# main.net
KiCad netlist of a schematic drawn in Altium Designer
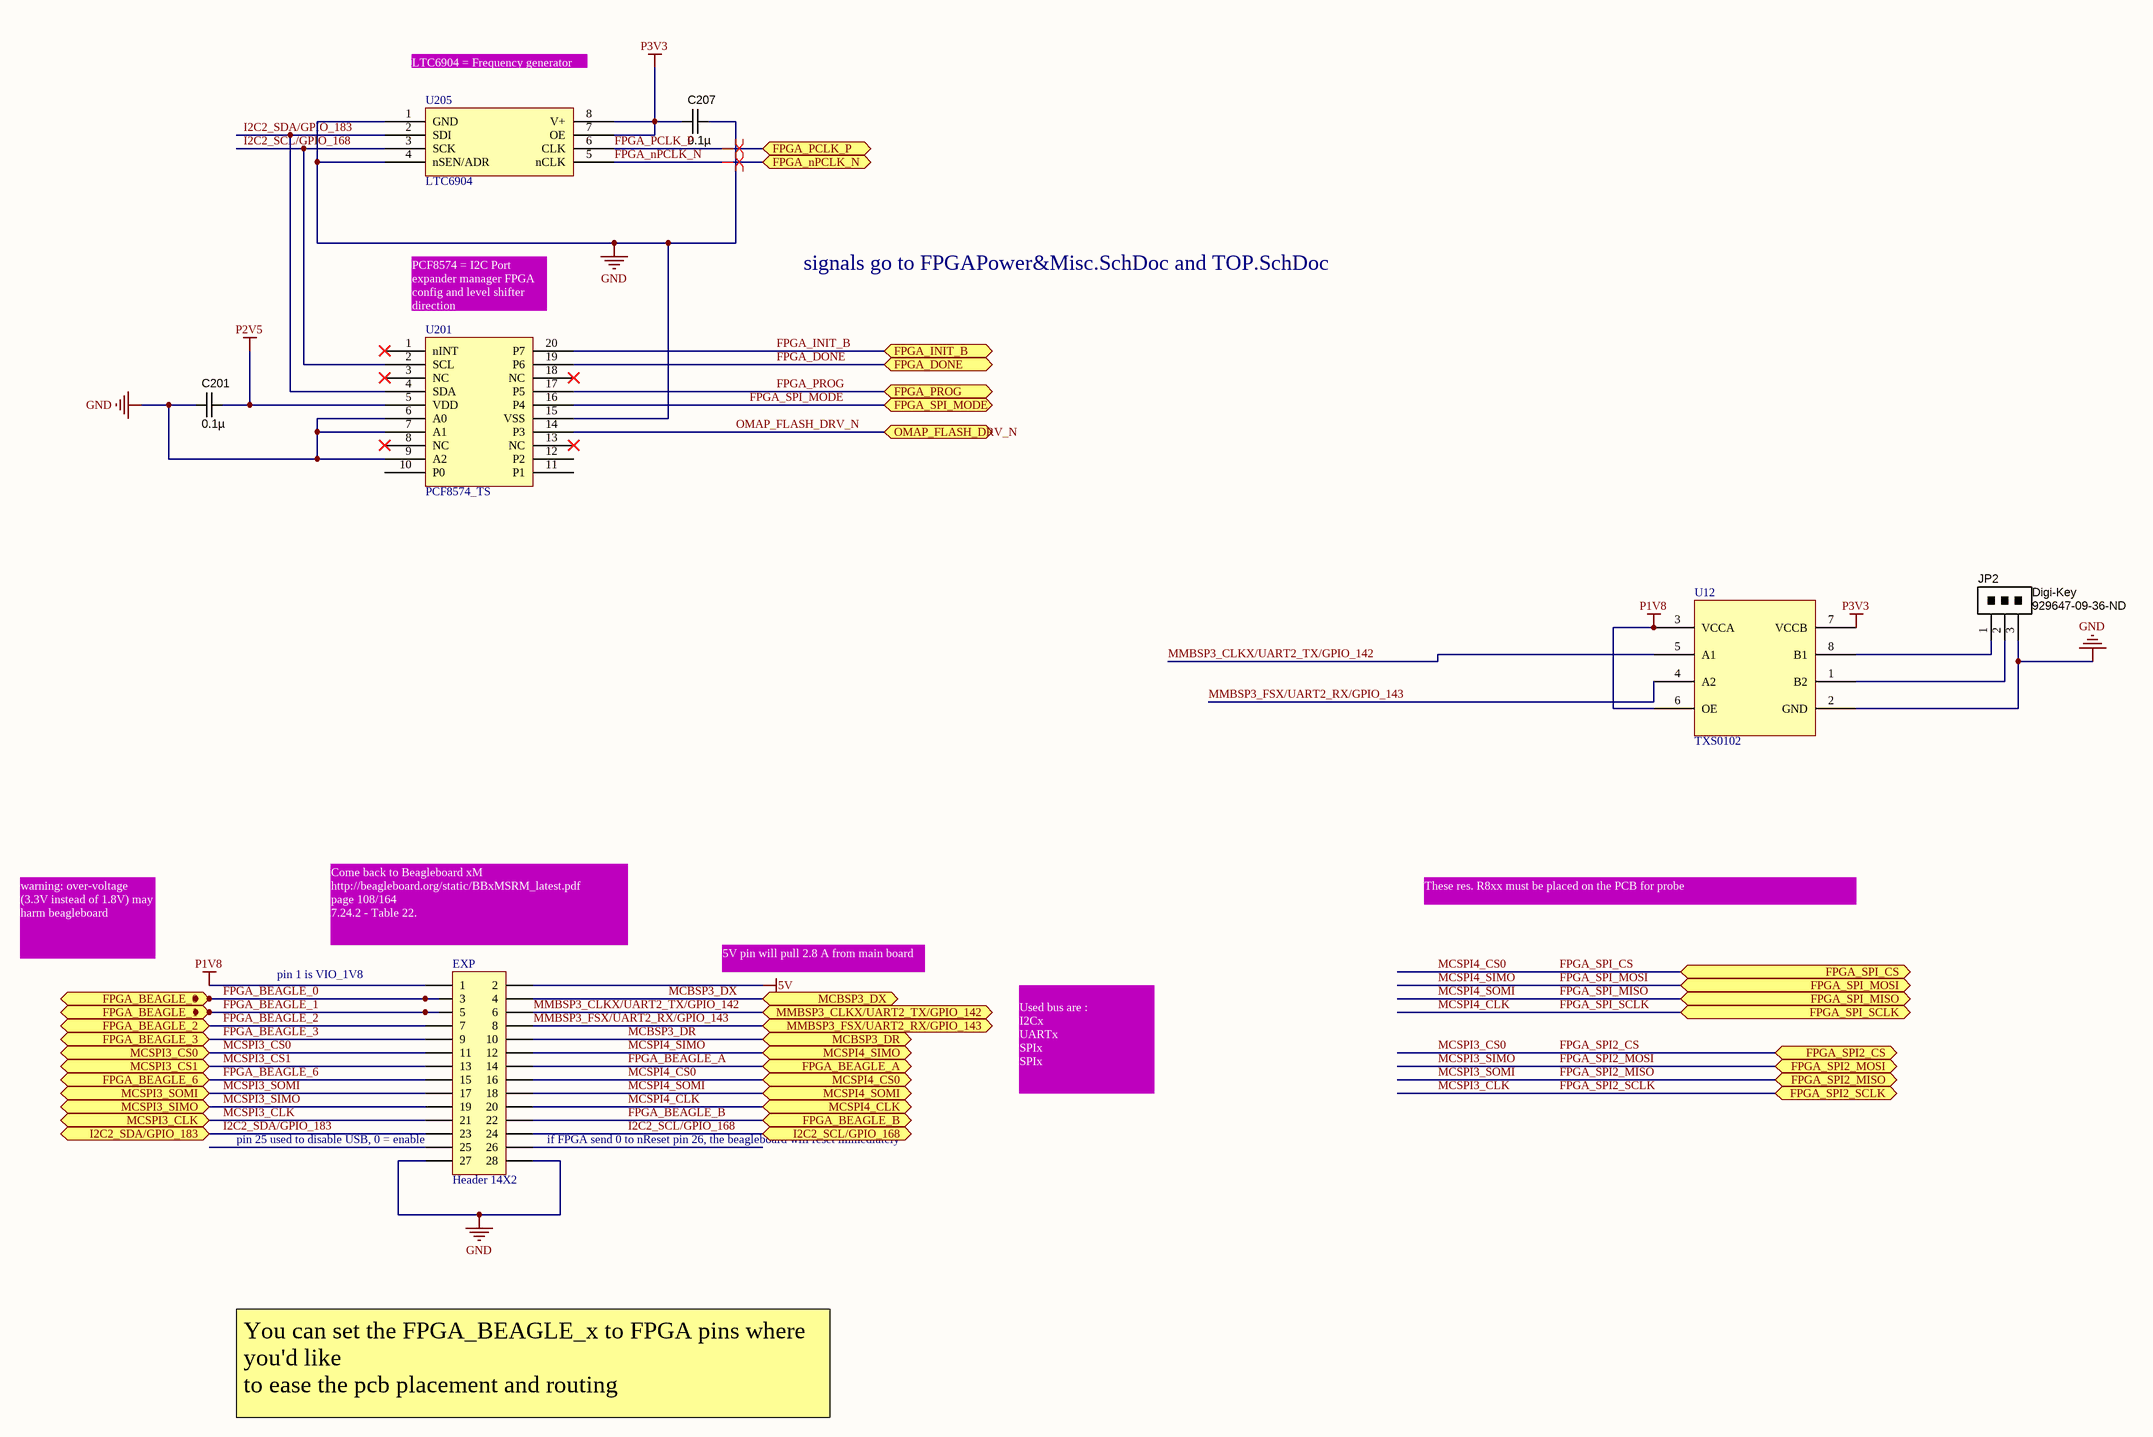
[diagram p0: main.schdoc]

(export (version "E")
  (design (tool "Eeschema 10.0.6"))
  (components
    (comp (ref "C201")
      (value "0.1µ")
      (footprint "CAPC1005X55N")
      (description "Capacitor SMD Cer 1uF 10% 16V X5R 0402")
      (fields (field (name "TOLERANCE") "±10%"))
      (libsource (lib "PBL - Capacitors") (part "CAPC_1u_0402_X5R_6V3_10%"))
    )
    (comp (ref "C207")
      (value "0.1µ")
      (footprint "CAPC1005X55N")
      (description "Capacitor SMD Cer 1uF 10% 16V X5R 0402")
      (fields (field (name "TOLERANCE") "±10%"))
      (libsource (lib "PBL - Capacitors") (part "CAPC_1u_0402_X5R_6V3_10%"))
    )
    (comp (ref "EXP")
      (value "Header 14X2")
      (footprint "HDR2X14")
      (description "Header, 14-Pin, Dual row")
      (fields (field (name "PUBLISHER") "Altium Limited"))
      (libsource (lib "Miscellaneous Connectors") (part "Header 14X2"))
    )
    (comp (ref "JP2")
      (value "R T G")
      (footprint "1x3POS_HEADER")
      (description "Pin Header, THT, Single-row, 2.54mm pitch")
      (fields
        (field (name "SUPPLIER 1") "Digi-Key")
        (field (name "SUPPLIER PART NUMBER 1") "929647-09-36-ND")
      )
      (libsource (lib "PBL - Connectors") (part "CONN_HEADER_1x3P_0.100in"))
    )
    (comp (ref "U12")
      (value "TXS0102")
      (footprint "TSSOP65P400X110-8N")
      (libsource (lib "beagle_sdr9_1") (part "TXS0102"))
    )
    (comp (ref "U201")
      (value "PCF8574_TS")
      (footprint "TSSOP65P640X120-20N")
      (libsource (lib "PCF8574_TS") (part "PCF8574_TS"))
    )
    (comp (ref "U205")
      (value "LTC6904")
      (footprint "SOP65P490X109-8N")
      (libsource (lib "LTC6904") (part "LTC6904"))
    )
  )
  (nets
    (net (code "1") (name "/FPGA_BEAGLE_0") (class "Default")
      (node (ref "EXP") (pin "3") (pinfunction "3_3") (pintype "passive"))
    )
    (net (code "2") (name "/FPGA_BEAGLE_1") (class "Default")
      (node (ref "EXP") (pin "5") (pinfunction "5_5") (pintype "passive"))
    )
    (net (code "3") (name "/FPGA_BEAGLE_2") (class "Default")
      (node (ref "EXP") (pin "7") (pinfunction "7_7") (pintype "passive"))
    )
    (net (code "4") (name "/FPGA_BEAGLE_3") (class "Default")
      (node (ref "EXP") (pin "9") (pinfunction "9_9") (pintype "passive"))
    )
    (net (code "5") (name "/FPGA_BEAGLE_6") (class "Default")
      (node (ref "EXP") (pin "15") (pinfunction "15_15") (pintype "passive"))
    )
    (net (code "6") (name "/FPGA_BEAGLE_A") (class "Default")
      (node (ref "EXP") (pin "14") (pinfunction "14_14") (pintype "passive"))
    )
    (net (code "7") (name "/FPGA_BEAGLE_B") (class "Default")
      (node (ref "EXP") (pin "22") (pinfunction "22_22") (pintype "passive"))
    )
    (net (code "8") (name "/FPGA_DONE") (class "Default")
      (node (ref "U201") (pin "19") (pinfunction "P6_19") (pintype "passive"))
    )
    (net (code "9") (name "/FPGA_INIT_B") (class "Default")
      (node (ref "U201") (pin "20") (pinfunction "P7_20") (pintype "passive"))
    )
    (net (code "10") (name "/FPGA_PCLK_P") (class "Default")
      (node (ref "U205") (pin "6") (pinfunction "CLK_6") (pintype "passive"))
    )
    (net (code "11") (name "/FPGA_PROG") (class "Default")
      (node (ref "U201") (pin "17") (pinfunction "P5_17") (pintype "passive"))
    )
    (net (code "12") (name "/FPGA_SPI2_CS") (class "Default")
      (node (ref "EXP") (pin "11") (pinfunction "11_11") (pintype "passive"))
    )
    (net (code "13") (name "/FPGA_SPI2_MISO") (class "Default")
      (node (ref "EXP") (pin "17") (pinfunction "17_17") (pintype "passive"))
    )
    (net (code "14") (name "/FPGA_SPI2_MOSI") (class "Default")
      (node (ref "EXP") (pin "19") (pinfunction "19_19") (pintype "passive"))
    )
    (net (code "15") (name "/FPGA_SPI2_SCLK") (class "Default")
      (node (ref "EXP") (pin "21") (pinfunction "21_21") (pintype "passive"))
    )
    (net (code "16") (name "/FPGA_SPI_CS") (class "Default")
      (node (ref "EXP") (pin "16") (pinfunction "16_16") (pintype "passive"))
    )
    (net (code "17") (name "/FPGA_SPI_MISO") (class "Default")
      (node (ref "EXP") (pin "18") (pinfunction "18_18") (pintype "passive"))
    )
    (net (code "18") (name "/FPGA_SPI_MODE") (class "Default")
      (node (ref "U201") (pin "16") (pinfunction "P4_16") (pintype "passive"))
    )
    (net (code "19") (name "/FPGA_SPI_MOSI") (class "Default")
      (node (ref "EXP") (pin "12") (pinfunction "12_12") (pintype "passive"))
    )
    (net (code "20") (name "/FPGA_SPI_SCLK") (class "Default")
      (node (ref "EXP") (pin "20") (pinfunction "20_20") (pintype "passive"))
    )
    (net (code "21") (name "/FPGA_nPCLK_N") (class "Default")
      (node (ref "U205") (pin "5") (pinfunction "nCLK_5") (pintype "passive"))
    )
    (net (code "22") (name "/I2C2_SCL{slash}GPIO_168") (class "Default")
      (node (ref "EXP") (pin "24") (pinfunction "24_24") (pintype "passive"))
      (node (ref "U201") (pin "2") (pinfunction "SCL_2") (pintype "passive"))
      (node (ref "U205") (pin "3") (pinfunction "SCK_3") (pintype "passive"))
    )
    (net (code "23") (name "/I2C2_SDA{slash}GPIO_183") (class "Default")
      (node (ref "EXP") (pin "23") (pinfunction "23_23") (pintype "passive"))
      (node (ref "U201") (pin "4") (pinfunction "SDA_4") (pintype "passive"))
      (node (ref "U205") (pin "2") (pinfunction "SDI_2") (pintype "passive"))
    )
    (net (code "24") (name "/MCBSP3_DR") (class "Default")
      (node (ref "EXP") (pin "10") (pinfunction "10_10") (pintype "passive"))
    )
    (net (code "25") (name "/MCBSP3_DX") (class "Default")
      (node (ref "EXP") (pin "4") (pinfunction "4_4") (pintype "passive"))
    )
    (net (code "26") (name "/MCSPI3_CS1") (class "Default")
      (node (ref "EXP") (pin "13") (pinfunction "13_13") (pintype "passive"))
    )
    (net (code "27") (name "/MMBSP3_CLKX{slash}UART2_TX{slash}GPIO_142") (class "Default")
      (node (ref "EXP") (pin "6") (pinfunction "6_6") (pintype "passive"))
      (node (ref "U12") (pin "5") (pinfunction "A1_5") (pintype "passive"))
    )
    (net (code "28") (name "/MMBSP3_FSX{slash}UART2_RX{slash}GPIO_143") (class "Default")
      (node (ref "EXP") (pin "8") (pinfunction "8_8") (pintype "passive"))
      (node (ref "U12") (pin "4") (pinfunction "A2_4") (pintype "passive"))
    )
    (net (code "29") (name "/OMAP_FLASH_DRV_N") (class "Default")
      (node (ref "U201") (pin "14") (pinfunction "P3_14") (pintype "passive"))
    )
    (net (code "30") (name "5V") (class "Default")
      (node (ref "EXP") (pin "2") (pinfunction "2_2") (pintype "passive"))
    )
    (net (code "31") (name "GND") (class "Default")
      (node (ref "C201") (pin "2") (pintype "passive"))
      (node (ref "C207") (pin "1") (pintype "passive"))
      (node (ref "EXP") (pin "27") (pinfunction "27_27") (pintype "passive"))
      (node (ref "EXP") (pin "28") (pinfunction "28_28") (pintype "passive"))
      (node (ref "JP2") (pin "3") (pinfunction "3_3") (pintype "passive"))
      (node (ref "U12") (pin "2") (pinfunction "GND_2") (pintype "passive"))
      (node (ref "U201") (pin "15") (pinfunction "VSS_15") (pintype "passive"))
      (node (ref "U201") (pin "6") (pinfunction "A0_6") (pintype "passive"))
      (node (ref "U201") (pin "7") (pinfunction "A1_7") (pintype "passive"))
      (node (ref "U201") (pin "9") (pinfunction "A2_9") (pintype "passive"))
      (node (ref "U205") (pin "1") (pinfunction "GND_1") (pintype "passive"))
      (node (ref "U205") (pin "4") (pinfunction "nSEN/ADR_4") (pintype "passive"))
    )
    (net (code "32") (name "Net-(U12-B1)") (class "Default")
      (node (ref "JP2") (pin "1") (pinfunction "1_1") (pintype "passive"))
      (node (ref "U12") (pin "8") (pinfunction "B1_8") (pintype "passive"))
    )
    (net (code "33") (name "Net-(U12-B2)") (class "Default")
      (node (ref "JP2") (pin "2") (pinfunction "2_2") (pintype "passive"))
      (node (ref "U12") (pin "1") (pinfunction "B2_1") (pintype "passive"))
    )
    (net (code "34") (name "P1V8") (class "Default")
      (node (ref "EXP") (pin "1") (pinfunction "1_1") (pintype "passive"))
      (node (ref "U12") (pin "3") (pinfunction "VCCA_3") (pintype "passive"))
      (node (ref "U12") (pin "6") (pinfunction "OE_6") (pintype "passive"))
    )
    (net (code "35") (name "P2V5") (class "Default")
      (node (ref "C201") (pin "1") (pintype "passive"))
      (node (ref "U201") (pin "5") (pinfunction "VDD_5") (pintype "passive"))
    )
    (net (code "36") (name "P3V3") (class "Default")
      (node (ref "C207") (pin "2") (pintype "passive"))
      (node (ref "U12") (pin "7") (pinfunction "VCCB_7") (pintype "passive"))
      (node (ref "U205") (pin "7") (pinfunction "OE_7") (pintype "passive"))
      (node (ref "U205") (pin "8") (pinfunction "V+_8") (pintype "passive"))
    )
    (net (code "37") (name "unconnected-(EXP-Pad25)") (class "Default")
      (node (ref "EXP") (pin "25") (pinfunction "25_25") (pintype "passive"))
    )
    (net (code "38") (name "unconnected-(EXP-Pad26)") (class "Default")
      (node (ref "EXP") (pin "26") (pinfunction "26_26") (pintype "passive"))
    )
    (net (code "39") (name "unconnected-(U201-NC-Pad3)") (class "Default")
      (node (ref "U201") (pin "3") (pinfunction "NC_3") (pintype "passive+no_connect"))
    )
    (net (code "40") (name "unconnected-(U201-NC-Pad8)") (class "Default")
      (node (ref "U201") (pin "8") (pinfunction "NC_8") (pintype "passive+no_connect"))
    )
    (net (code "41") (name "unconnected-(U201-NC-Pad13)") (class "Default")
      (node (ref "U201") (pin "13") (pinfunction "NC_13") (pintype "passive+no_connect"))
    )
    (net (code "42") (name "unconnected-(U201-NC-Pad18)") (class "Default")
      (node (ref "U201") (pin "18") (pinfunction "NC_18") (pintype "passive+no_connect"))
    )
    (net (code "43") (name "unconnected-(U201-P0-Pad10)") (class "Default")
      (node (ref "U201") (pin "10") (pinfunction "P0_10") (pintype "passive"))
    )
    (net (code "44") (name "unconnected-(U201-P1-Pad11)") (class "Default")
      (node (ref "U201") (pin "11") (pinfunction "P1_11") (pintype "passive"))
    )
    (net (code "45") (name "unconnected-(U201-P2-Pad12)") (class "Default")
      (node (ref "U201") (pin "12") (pinfunction "P2_12") (pintype "passive"))
    )
    (net (code "46") (name "unconnected-(U201-nINT-Pad1)") (class "Default")
      (node (ref "U201") (pin "1") (pinfunction "nINT_1") (pintype "passive+no_connect"))
    )
  )
)
